# logic_alpha0001.net
KiCad netlist of a schematic drawn in EAGLE
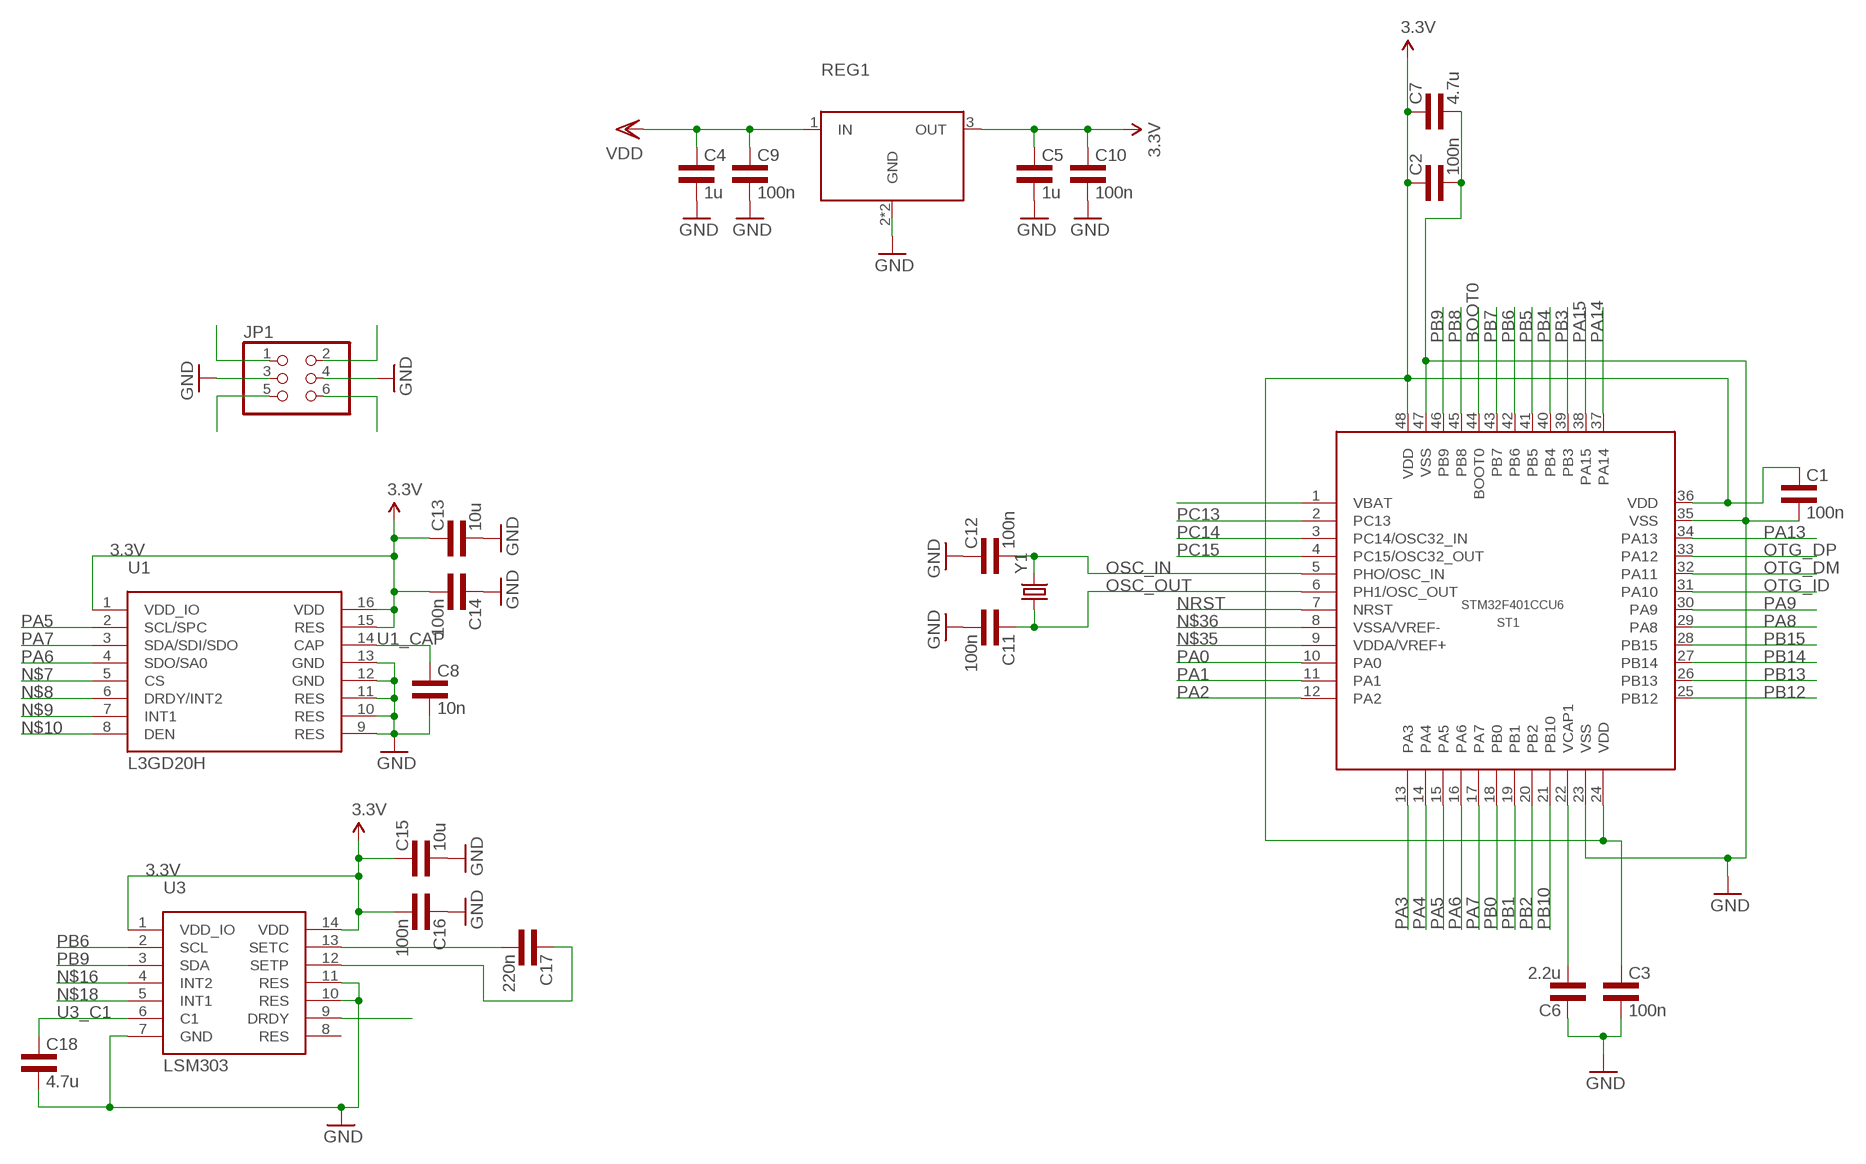
[diagram p0: schematic, sheet 1]

(export (version "E")
  (design (tool "Eeschema 10.0.6"))
  (components
    (comp (ref "C1")
      (value "100n")
      (footprint "eagle-import:0402L3")
      (libsource (lib "eagle-import") (part "CAP0402L3"))
    )
    (comp (ref "C2")
      (value "100n")
      (footprint "eagle-import:0402L3")
      (libsource (lib "eagle-import") (part "CAP0402L3"))
    )
    (comp (ref "C3")
      (value "100n")
      (footprint "eagle-import:0402L3")
      (libsource (lib "eagle-import") (part "CAP0402L3"))
    )
    (comp (ref "C4")
      (value "1u")
      (footprint "eagle-import:0805L3")
      (libsource (lib "eagle-import") (part "CAP0805L3"))
    )
    (comp (ref "C5")
      (value "1u")
      (footprint "eagle-import:0805L3")
      (libsource (lib "eagle-import") (part "CAP0805L3"))
    )
    (comp (ref "C6")
      (value "2.2u")
      (footprint "eagle-import:0402L3")
      (libsource (lib "eagle-import") (part "CAP0402L3"))
    )
    (comp (ref "C7")
      (value "4.7u")
      (footprint "eagle-import:0805L3")
      (libsource (lib "eagle-import") (part "CAP0805L3"))
    )
    (comp (ref "C8")
      (value "10n")
      (footprint "eagle-import:0603L3")
      (libsource (lib "eagle-import") (part "CAP0603L3"))
    )
    (comp (ref "C9")
      (value "100n")
      (footprint "eagle-import:0603L3")
      (libsource (lib "eagle-import") (part "CAP0603L3"))
    )
    (comp (ref "C10")
      (value "100n")
      (footprint "eagle-import:0603L3")
      (libsource (lib "eagle-import") (part "CAP0603L3"))
    )
    (comp (ref "C11")
      (value "100n")
      (footprint "eagle-import:0402L3")
      (libsource (lib "eagle-import") (part "CAP0402L3"))
    )
    (comp (ref "C12")
      (value "100n")
      (footprint "eagle-import:0402L3")
      (libsource (lib "eagle-import") (part "CAP0402L3"))
    )
    (comp (ref "C13")
      (value "10u")
      (footprint "eagle-import:0805L3")
      (libsource (lib "eagle-import") (part "CAP0805L3"))
    )
    (comp (ref "C14")
      (value "100n")
      (footprint "eagle-import:0603L3")
      (libsource (lib "eagle-import") (part "CAP0603L3"))
    )
    (comp (ref "C15")
      (value "10u")
      (footprint "eagle-import:0805L3")
      (libsource (lib "eagle-import") (part "CAP0805L3"))
    )
    (comp (ref "C16")
      (value "100n")
      (footprint "eagle-import:0603L3")
      (libsource (lib "eagle-import") (part "CAP0603L3"))
    )
    (comp (ref "C17")
      (value "220n")
      (footprint "eagle-import:0603L3")
      (libsource (lib "eagle-import") (part "CAP0603L3"))
    )
    (comp (ref "C18")
      (value "4.7u")
      (footprint "eagle-import:0603L3")
      (libsource (lib "eagle-import") (part "CAP0603L3"))
    )
    (comp (ref "JP1")
      (value "PINHD-2X3")
      (footprint "eagle-import:2X03")
      (libsource (lib "eagle-import") (part "PINHD-2X3"))
    )
    (comp (ref "REG1")
      (value "LDO_REG_4PIN")
      (footprint "eagle-import:SOT-223-3")
      (libsource (lib "eagle-import") (part "LDO_REG_4PIN"))
    )
    (comp (ref "ST1")
      (value "STM32F401CCU6")
      (footprint "eagle-import:UFQFPN48")
      (libsource (lib "eagle-import") (part "STM32F401CCU6"))
    )
    (comp (ref "U1")
      (value "L3GD20H")
      (footprint "eagle-import:LGA16R50P3X5_300X300X100")
      (libsource (lib "eagle-import") (part "L3GD20H"))
    )
    (comp (ref "U3")
      (value "LSM303")
      (footprint "eagle-import:LGA14")
      (libsource (lib "eagle-import") (part "LSM303"))
    )
    (comp (ref "Y1")
      (value "CRYSTALHC49US")
      (footprint "eagle-import:HC49US")
      (libsource (lib "eagle-import") (part "CRYSTALHC49US"))
    )
  )
  (nets
    (net (code "1") (name "/BOOT0") (class "Default")
      (node (ref "ST1") (pin "44") (pinfunction "BOOT0_44") (pintype "bidirectional"))
    )
    (net (code "2") (name "/N$7") (class "Default")
      (node (ref "U1") (pin "5") (pinfunction "CS_5") (pintype "bidirectional"))
    )
    (net (code "3") (name "/N$8") (class "Default")
      (node (ref "U1") (pin "6") (pinfunction "DRDY/INT2_6") (pintype "bidirectional"))
    )
    (net (code "4") (name "/N$9") (class "Default")
      (node (ref "U1") (pin "7") (pinfunction "INT1_7") (pintype "bidirectional"))
    )
    (net (code "5") (name "/N$10") (class "Default")
      (node (ref "U1") (pin "8") (pinfunction "DEN_8") (pintype "bidirectional"))
    )
    (net (code "6") (name "/N$16") (class "Default")
      (node (ref "U3") (pin "4") (pinfunction "INT2_4") (pintype "bidirectional"))
    )
    (net (code "7") (name "/N$18") (class "Default")
      (node (ref "U3") (pin "5") (pinfunction "INT1_5") (pintype "bidirectional"))
    )
    (net (code "8") (name "/N$35") (class "Default")
      (node (ref "ST1") (pin "9") (pinfunction "VDDA/VREF+_9") (pintype "bidirectional"))
    )
    (net (code "9") (name "/N$36") (class "Default")
      (node (ref "ST1") (pin "8") (pinfunction "VSSA/VREF-_8") (pintype "bidirectional"))
    )
    (net (code "10") (name "/NRST") (class "Default")
      (node (ref "ST1") (pin "7") (pinfunction "NRST_7") (pintype "bidirectional"))
    )
    (net (code "11") (name "/OSC_IN") (class "Default")
      (node (ref "C12") (pin "P$2") (pinfunction "2_P$2") (pintype "bidirectional"))
      (node (ref "ST1") (pin "5") (pinfunction "PHO/OSC_IN_5") (pintype "bidirectional"))
      (node (ref "Y1") (pin "2") (pinfunction "2_2") (pintype "passive"))
    )
    (net (code "12") (name "/OSC_OUT") (class "Default")
      (node (ref "C11") (pin "P$1") (pinfunction "1_P$1") (pintype "bidirectional"))
      (node (ref "ST1") (pin "6") (pinfunction "PH1/OSC_OUT_6") (pintype "bidirectional"))
      (node (ref "Y1") (pin "1") (pinfunction "1_1") (pintype "passive"))
    )
    (net (code "13") (name "/OTG_DM") (class "Default")
      (node (ref "ST1") (pin "32") (pinfunction "PA11_32") (pintype "bidirectional"))
    )
    (net (code "14") (name "/OTG_DP") (class "Default")
      (node (ref "ST1") (pin "33") (pinfunction "PA12_33") (pintype "bidirectional"))
    )
    (net (code "15") (name "/OTG_ID") (class "Default")
      (node (ref "ST1") (pin "31") (pinfunction "PA10_31") (pintype "bidirectional"))
    )
    (net (code "16") (name "/PA0") (class "Default")
      (node (ref "ST1") (pin "10") (pinfunction "PA0_10") (pintype "bidirectional"))
    )
    (net (code "17") (name "/PA1") (class "Default")
      (node (ref "ST1") (pin "11") (pinfunction "PA1_11") (pintype "bidirectional"))
    )
    (net (code "18") (name "/PA2") (class "Default")
      (node (ref "ST1") (pin "12") (pinfunction "PA2_12") (pintype "bidirectional"))
    )
    (net (code "19") (name "/PA3") (class "Default")
      (node (ref "ST1") (pin "13") (pinfunction "PA3_13") (pintype "bidirectional"))
    )
    (net (code "20") (name "/PA4") (class "Default")
      (node (ref "ST1") (pin "14") (pinfunction "PA4_14") (pintype "bidirectional"))
    )
    (net (code "21") (name "/PA5") (class "Default")
      (node (ref "ST1") (pin "15") (pinfunction "PA5_15") (pintype "bidirectional"))
      (node (ref "U1") (pin "2") (pinfunction "SCL/SPC_2") (pintype "bidirectional"))
    )
    (net (code "22") (name "/PA6") (class "Default")
      (node (ref "ST1") (pin "16") (pinfunction "PA6_16") (pintype "bidirectional"))
      (node (ref "U1") (pin "4") (pinfunction "SDO/SA0_4") (pintype "bidirectional"))
    )
    (net (code "23") (name "/PA7") (class "Default")
      (node (ref "ST1") (pin "17") (pinfunction "PA7_17") (pintype "bidirectional"))
      (node (ref "U1") (pin "3") (pinfunction "SDA/SDI/SDO_3") (pintype "bidirectional"))
    )
    (net (code "24") (name "/PA8") (class "Default")
      (node (ref "ST1") (pin "29") (pinfunction "PA8_29") (pintype "bidirectional"))
    )
    (net (code "25") (name "/PA9") (class "Default")
      (node (ref "ST1") (pin "30") (pinfunction "PA9_30") (pintype "bidirectional"))
    )
    (net (code "26") (name "/PA13") (class "Default")
      (node (ref "ST1") (pin "34") (pinfunction "PA13_34") (pintype "bidirectional"))
    )
    (net (code "27") (name "/PA14") (class "Default")
      (node (ref "ST1") (pin "37") (pinfunction "PA14_37") (pintype "bidirectional"))
    )
    (net (code "28") (name "/PA15") (class "Default")
      (node (ref "ST1") (pin "38") (pinfunction "PA15_38") (pintype "bidirectional"))
    )
    (net (code "29") (name "/PB0") (class "Default")
      (node (ref "ST1") (pin "18") (pinfunction "PB0_18") (pintype "bidirectional"))
    )
    (net (code "30") (name "/PB1") (class "Default")
      (node (ref "ST1") (pin "19") (pinfunction "PB1_19") (pintype "bidirectional"))
    )
    (net (code "31") (name "/PB2") (class "Default")
      (node (ref "ST1") (pin "20") (pinfunction "PB2_20") (pintype "bidirectional"))
    )
    (net (code "32") (name "/PB3") (class "Default")
      (node (ref "ST1") (pin "39") (pinfunction "PB3_39") (pintype "bidirectional"))
    )
    (net (code "33") (name "/PB4") (class "Default")
      (node (ref "ST1") (pin "40") (pinfunction "PB4_40") (pintype "bidirectional"))
    )
    (net (code "34") (name "/PB5") (class "Default")
      (node (ref "ST1") (pin "41") (pinfunction "PB5_41") (pintype "bidirectional"))
    )
    (net (code "35") (name "/PB6") (class "Default")
      (node (ref "ST1") (pin "42") (pinfunction "PB6_42") (pintype "bidirectional"))
      (node (ref "U3") (pin "2") (pinfunction "SCL_2") (pintype "bidirectional"))
    )
    (net (code "36") (name "/PB7") (class "Default")
      (node (ref "ST1") (pin "43") (pinfunction "PB7_43") (pintype "bidirectional"))
    )
    (net (code "37") (name "/PB8") (class "Default")
      (node (ref "ST1") (pin "45") (pinfunction "PB8_45") (pintype "bidirectional"))
    )
    (net (code "38") (name "/PB9") (class "Default")
      (node (ref "ST1") (pin "46") (pinfunction "PB9_46") (pintype "bidirectional"))
      (node (ref "U3") (pin "3") (pinfunction "SDA_3") (pintype "bidirectional"))
    )
    (net (code "39") (name "/PB10") (class "Default")
      (node (ref "ST1") (pin "21") (pinfunction "PB10_21") (pintype "bidirectional"))
    )
    (net (code "40") (name "/PB12") (class "Default")
      (node (ref "ST1") (pin "25") (pinfunction "PB12_25") (pintype "bidirectional"))
    )
    (net (code "41") (name "/PB13") (class "Default")
      (node (ref "ST1") (pin "26") (pinfunction "PB13_26") (pintype "bidirectional"))
    )
    (net (code "42") (name "/PB14") (class "Default")
      (node (ref "ST1") (pin "27") (pinfunction "PB14_27") (pintype "bidirectional"))
    )
    (net (code "43") (name "/PB15") (class "Default")
      (node (ref "ST1") (pin "28") (pinfunction "PB15_28") (pintype "bidirectional"))
    )
    (net (code "44") (name "/PC13") (class "Default")
      (node (ref "ST1") (pin "2") (pinfunction "PC13_2") (pintype "bidirectional"))
    )
    (net (code "45") (name "/PC14") (class "Default")
      (node (ref "ST1") (pin "3") (pinfunction "PC14/OSC32_IN_3") (pintype "bidirectional"))
    )
    (net (code "46") (name "/PC15") (class "Default")
      (node (ref "ST1") (pin "4") (pinfunction "PC15/OSC32_OUT_4") (pintype "bidirectional"))
    )
    (net (code "47") (name "/U1_CAP") (class "Default")
      (node (ref "C8") (pin "P$1") (pinfunction "1_P$1") (pintype "bidirectional"))
      (node (ref "U1") (pin "14") (pinfunction "CAP_14") (pintype "bidirectional"))
    )
    (net (code "48") (name "/U3_C1") (class "Default")
      (node (ref "C18") (pin "P$1") (pinfunction "1_P$1") (pintype "bidirectional"))
      (node (ref "U3") (pin "6") (pinfunction "C1_6") (pintype "bidirectional"))
    )
    (net (code "49") (name "3.3V") (class "Default")
      (node (ref "C1") (pin "P$1") (pinfunction "1_P$1") (pintype "bidirectional"))
      (node (ref "C10") (pin "P$1") (pinfunction "1_P$1") (pintype "bidirectional"))
      (node (ref "C13") (pin "1") (pinfunction "1_1") (pintype "bidirectional"))
      (node (ref "C14") (pin "P$2") (pinfunction "2_P$2") (pintype "bidirectional"))
      (node (ref "C15") (pin "1") (pinfunction "1_1") (pintype "bidirectional"))
      (node (ref "C16") (pin "P$2") (pinfunction "2_P$2") (pintype "bidirectional"))
      (node (ref "C2") (pin "P$1") (pinfunction "1_P$1") (pintype "bidirectional"))
      (node (ref "C3") (pin "P$1") (pinfunction "1_P$1") (pintype "bidirectional"))
      (node (ref "C5") (pin "1") (pinfunction "1_1") (pintype "bidirectional"))
      (node (ref "C7") (pin "1") (pinfunction "1_1") (pintype "bidirectional"))
      (node (ref "REG1") (pin "3") (pinfunction "OUT_3") (pintype "bidirectional"))
      (node (ref "ST1") (pin "24") (pinfunction "VDD_24") (pintype "bidirectional"))
      (node (ref "ST1") (pin "36") (pinfunction "VDD_36") (pintype "bidirectional"))
      (node (ref "ST1") (pin "48") (pinfunction "VDD_48") (pintype "bidirectional"))
      (node (ref "U1") (pin "1") (pinfunction "VDD_IO_1") (pintype "bidirectional"))
      (node (ref "U1") (pin "15") (pinfunction "RES_15") (pintype "bidirectional"))
      (node (ref "U1") (pin "16") (pinfunction "VDD_16") (pintype "bidirectional"))
      (node (ref "U3") (pin "1") (pinfunction "VDD_IO_1") (pintype "bidirectional"))
      (node (ref "U3") (pin "14") (pinfunction "VDD_14") (pintype "bidirectional"))
    )
    (net (code "50") (name "GND") (class "Default")
      (node (ref "C1") (pin "P$2") (pinfunction "2_P$2") (pintype "bidirectional"))
      (node (ref "C10") (pin "P$2") (pinfunction "2_P$2") (pintype "bidirectional"))
      (node (ref "C11") (pin "P$2") (pinfunction "2_P$2") (pintype "bidirectional"))
      (node (ref "C12") (pin "P$1") (pinfunction "1_P$1") (pintype "bidirectional"))
      (node (ref "C13") (pin "2") (pinfunction "2_2") (pintype "bidirectional"))
      (node (ref "C14") (pin "P$1") (pinfunction "1_P$1") (pintype "bidirectional"))
      (node (ref "C15") (pin "2") (pinfunction "2_2") (pintype "bidirectional"))
      (node (ref "C16") (pin "P$1") (pinfunction "1_P$1") (pintype "bidirectional"))
      (node (ref "C18") (pin "P$2") (pinfunction "2_P$2") (pintype "bidirectional"))
      (node (ref "C2") (pin "P$2") (pinfunction "2_P$2") (pintype "bidirectional"))
      (node (ref "C3") (pin "P$2") (pinfunction "2_P$2") (pintype "bidirectional"))
      (node (ref "C4") (pin "2") (pinfunction "2_2") (pintype "bidirectional"))
      (node (ref "C5") (pin "2") (pinfunction "2_2") (pintype "bidirectional"))
      (node (ref "C6") (pin "P$1") (pinfunction "1_P$1") (pintype "bidirectional"))
      (node (ref "C7") (pin "2") (pinfunction "2_2") (pintype "bidirectional"))
      (node (ref "C8") (pin "P$2") (pinfunction "2_P$2") (pintype "bidirectional"))
      (node (ref "C9") (pin "P$2") (pinfunction "2_P$2") (pintype "bidirectional"))
      (node (ref "JP1") (pin "3") (pinfunction "3_3") (pintype "passive"))
      (node (ref "JP1") (pin "4") (pinfunction "4_4") (pintype "passive"))
      (node (ref "REG1") (pin "2") (pinfunction "GND_2") (pintype "bidirectional"))
      (node (ref "REG1") (pin "4") (pinfunction "GND_4") (pintype "bidirectional"))
      (node (ref "ST1") (pin "23") (pinfunction "VSS_23") (pintype "bidirectional"))
      (node (ref "ST1") (pin "35") (pinfunction "VSS_35") (pintype "bidirectional"))
      (node (ref "ST1") (pin "47") (pinfunction "VSS_47") (pintype "bidirectional"))
      (node (ref "U1") (pin "10") (pinfunction "RES_10") (pintype "bidirectional"))
      (node (ref "U1") (pin "11") (pinfunction "RES_11") (pintype "bidirectional"))
      (node (ref "U1") (pin "12") (pinfunction "GND_12") (pintype "bidirectional"))
      (node (ref "U1") (pin "13") (pinfunction "GND_13") (pintype "bidirectional"))
      (node (ref "U1") (pin "9") (pinfunction "RES_9") (pintype "bidirectional"))
      (node (ref "U3") (pin "10") (pinfunction "RES_10") (pintype "bidirectional"))
      (node (ref "U3") (pin "11") (pinfunction "RES_11") (pintype "bidirectional"))
      (node (ref "U3") (pin "7") (pinfunction "GND_7") (pintype "bidirectional"))
    )
    (net (code "51") (name "Net-(C6-2)") (class "Default")
      (node (ref "C6") (pin "P$2") (pinfunction "2_P$2") (pintype "bidirectional"))
      (node (ref "ST1") (pin "22") (pinfunction "VCAP1_22") (pintype "bidirectional"))
    )
    (net (code "52") (name "Net-(C17-1)") (class "Default")
      (node (ref "C17") (pin "P$1") (pinfunction "1_P$1") (pintype "bidirectional"))
      (node (ref "U3") (pin "12") (pinfunction "SETP_12") (pintype "bidirectional"))
    )
    (net (code "53") (name "Net-(C17-2)") (class "Default")
      (node (ref "C17") (pin "P$2") (pinfunction "2_P$2") (pintype "bidirectional"))
      (node (ref "U3") (pin "13") (pinfunction "SETC_13") (pintype "bidirectional"))
    )
    (net (code "54") (name "VDD") (class "Default")
      (node (ref "C4") (pin "1") (pinfunction "1_1") (pintype "bidirectional"))
      (node (ref "C9") (pin "P$1") (pinfunction "1_P$1") (pintype "bidirectional"))
      (node (ref "REG1") (pin "1") (pinfunction "IN_1") (pintype "bidirectional"))
    )
    (net (code "55") (name "unconnected-(JP1-Pad1)") (class "Default")
      (node (ref "JP1") (pin "1") (pinfunction "1_1") (pintype "passive"))
    )
    (net (code "56") (name "unconnected-(JP1-Pad2)") (class "Default")
      (node (ref "JP1") (pin "2") (pinfunction "2_2") (pintype "passive"))
    )
    (net (code "57") (name "unconnected-(JP1-Pad5)") (class "Default")
      (node (ref "JP1") (pin "5") (pinfunction "5_5") (pintype "passive"))
    )
    (net (code "58") (name "unconnected-(JP1-Pad6)") (class "Default")
      (node (ref "JP1") (pin "6") (pinfunction "6_6") (pintype "passive"))
    )
    (net (code "59") (name "unconnected-(ST1-VBAT-Pad1)") (class "Default")
      (node (ref "ST1") (pin "1") (pinfunction "VBAT_1") (pintype "bidirectional"))
    )
    (net (code "60") (name "unconnected-(U3-DRDY-Pad9)") (class "Default")
      (node (ref "U3") (pin "9") (pinfunction "DRDY_9") (pintype "bidirectional"))
    )
    (net (code "61") (name "unconnected-(U3-RES-Pad8)") (class "Default")
      (node (ref "U3") (pin "8") (pinfunction "RES_8") (pintype "bidirectional"))
    )
  )
)
